# lane.net
KiCad netlist of a schematic drawn in Altium Designer
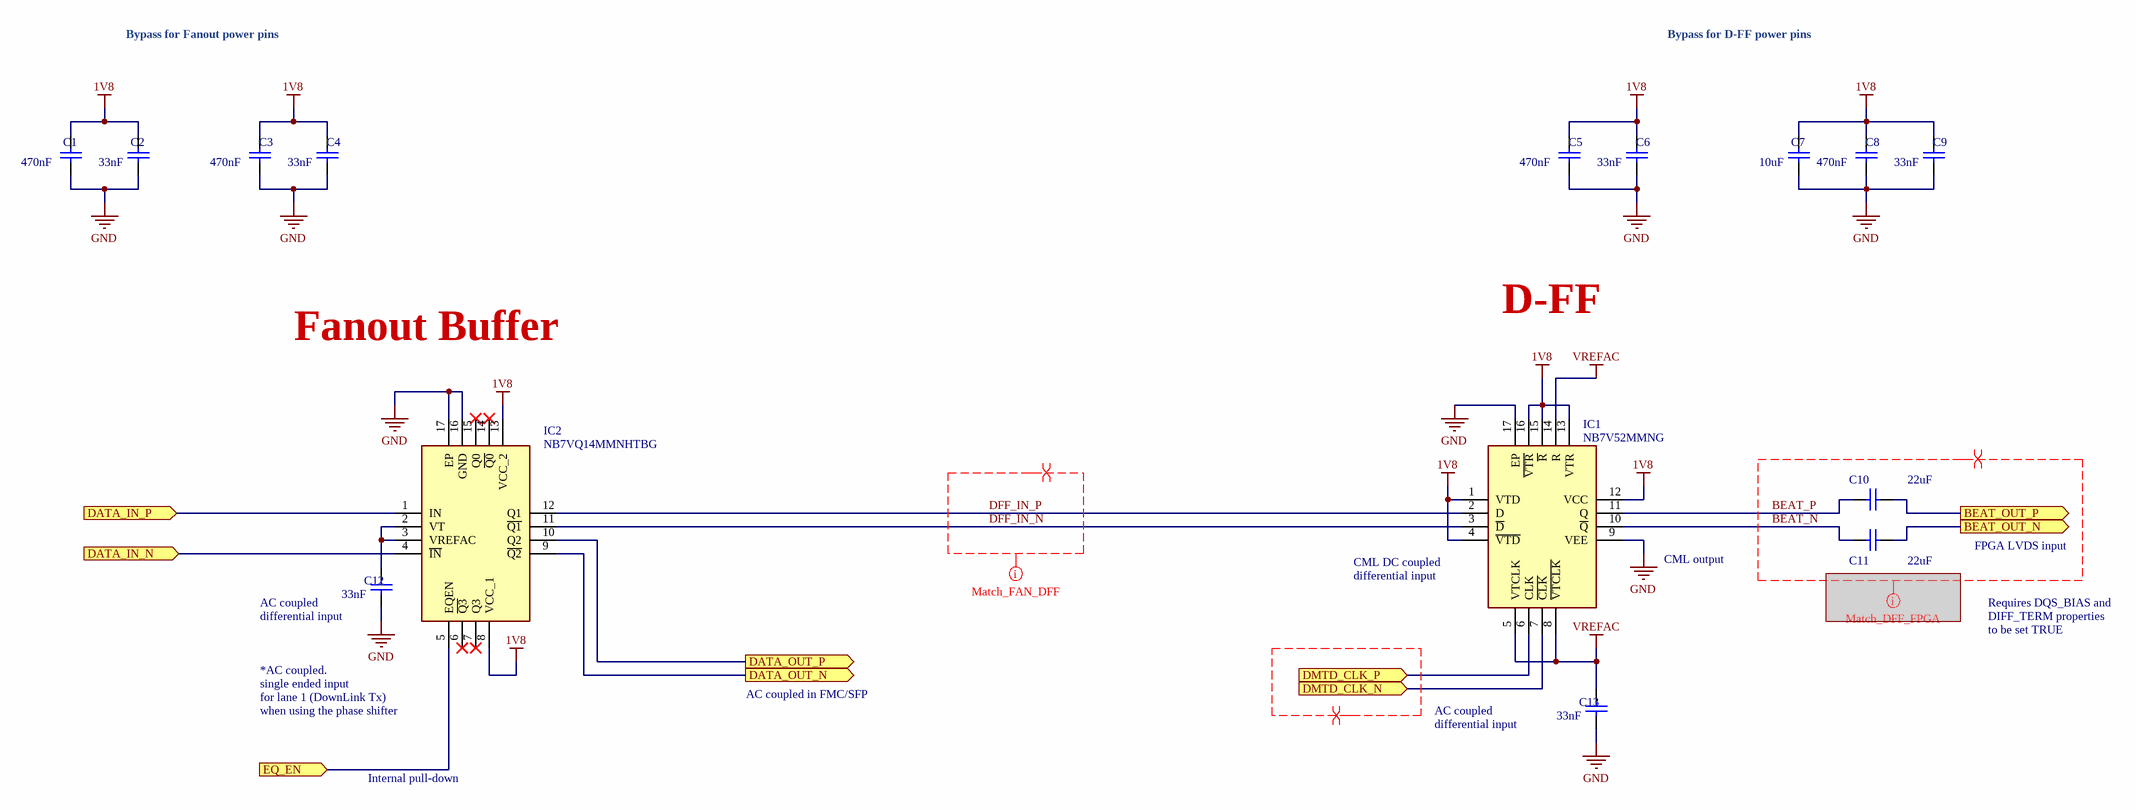
[diagram p0: lane.SchDoc]

(export (version "E")
  (design (tool "Eeschema 10.0.6"))
  (components
    (comp (ref "C1")
      (value "470nF")
      (footprint "CAPC0510X04N")
      (description "LLL153C70G474ME17")
      (libsource (lib "auxiliary_library") (part "Capacitor - non polarized"))
    )
    (comp (ref "C2")
      (value "33nF")
      (footprint "LLL03TR61E333KE01")
      (description "LLL03TR61E333KE01")
      (libsource (lib "auxiliary_library") (part "Capacitor - non polarized"))
    )
    (comp (ref "C3")
      (value "470nF")
      (footprint "CAPC0510X04N")
      (description "LLL153C70G474ME17")
      (libsource (lib "auxiliary_library") (part "Capacitor - non polarized"))
    )
    (comp (ref "C4")
      (value "33nF")
      (footprint "LLL03TR61E333KE01")
      (description "LLL03TR61E333KE01")
      (libsource (lib "auxiliary_library") (part "Capacitor - non polarized"))
    )
    (comp (ref "C5")
      (value "470nF")
      (footprint "CAPC0510X04N")
      (description "LLL153C70G474ME17")
      (libsource (lib "auxiliary_library") (part "Capacitor - non polarized"))
    )
    (comp (ref "C6")
      (value "33nF")
      (footprint "LLL03TR61E333KE01")
      (description "LLL03TR61E333KE01")
      (libsource (lib "auxiliary_library") (part "Capacitor - non polarized"))
    )
    (comp (ref "C7")
      (value "10uF")
      (footprint "CAPC1608X87N")
      (description "C1608X5R1E106M080AC")
      (fields
        (field (name "PART NUMBER") "CC0603_10UF_6.3V_20%_X5R")
        (field (name "VOLTAGE") "6.3V")
        (field (name "AUTHOR") "CERN DEM JLC")
      )
      (libsource (lib "Capacitors") (part "Capacitor - non polarized"))
    )
    (comp (ref "C8")
      (value "470nF")
      (footprint "CAPC0510X04N")
      (description "LLL153C70G474ME17")
      (libsource (lib "auxiliary_library") (part "Capacitor - non polarized"))
    )
    (comp (ref "C9")
      (value "33nF")
      (footprint "LLL03TR61E333KE01")
      (description "LLL03TR61E333KE01")
      (libsource (lib "auxiliary_library") (part "Capacitor - non polarized"))
    )
    (comp (ref "C10")
      (value "22uF")
      (footprint "MURATA_HI_DENSITY_0402_CAP")
      (description "GRM155R60J226ME11")
      (libsource (lib "schLib") (part "C0402-22uF-high-density"))
    )
    (comp (ref "C11")
      (value "22uF")
      (footprint "MURATA_HI_DENSITY_0402_CAP")
      (description "GRM155R60J226ME11")
      (libsource (lib "schLib") (part "C0402-22uF-high-density"))
    )
    (comp (ref "C12")
      (value "33nF")
      (footprint "LLL03TR61E333KE01")
      (description "LLL03TR61E333KE01")
      (libsource (lib "auxiliary_library") (part "Capacitor - non polarized"))
    )
    (comp (ref "C13")
      (value "33nF")
      (footprint "LLL03TR61E333KE01")
      (description "LLL03TR61E333KE01")
      (libsource (lib "auxiliary_library") (part "Capacitor - non polarized"))
    )
    (comp (ref "IC1")
      (value "NB7V52MMNG")
      (footprint "SamacSys:QFN50P300X300X100-17N")
      (description "Integrated Circuit")
      (fields (field (name "MOUSER PART NUMBER") "863-NB7V52MMNG"))
      (libsource (lib "SamacSys") (part "NB7V52MMNG"))
    )
    (comp (ref "IC2")
      (value "NB7VQ14MMNHTBG")
      (footprint "SamacSys:QFN50P300X300X100-17N")
      (description "Integrated Circuit")
      (fields (field (name "MOUSER PART NUMBER") "863-NB7VQ14MMNHTBG"))
      (libsource (lib "*") (part "NB7VQ14MMNHTBG"))
    )
  )
  (nets
    (net (code "1") (name "/BEAT_N") (class "Default")
      (node (ref "C11") (pin "2") (pinfunction "2_2") (pintype "passive"))
      (node (ref "IC1") (pin "10") (pinfunction "~{Q}_10") (pintype "passive"))
    )
    (net (code "2") (name "/BEAT_OUT_N") (class "Default")
      (node (ref "C11") (pin "1") (pinfunction "1_1") (pintype "passive"))
    )
    (net (code "3") (name "/BEAT_OUT_P") (class "Default")
      (node (ref "C10") (pin "1") (pinfunction "1_1") (pintype "passive"))
    )
    (net (code "4") (name "/BEAT_P") (class "Default")
      (node (ref "C10") (pin "2") (pinfunction "2_2") (pintype "passive"))
      (node (ref "IC1") (pin "11") (pinfunction "Q_11") (pintype "passive"))
    )
    (net (code "5") (name "/DATA_IN_N") (class "Default")
      (node (ref "IC2") (pin "4") (pinfunction "~{IN}_4") (pintype "passive"))
    )
    (net (code "6") (name "/DATA_IN_P") (class "Default")
      (node (ref "IC2") (pin "1") (pinfunction "IN_1") (pintype "passive"))
    )
    (net (code "7") (name "/DATA_OUT_N") (class "Default")
      (node (ref "IC2") (pin "9") (pinfunction "~{Q2}_9") (pintype "passive"))
    )
    (net (code "8") (name "/DATA_OUT_P") (class "Default")
      (node (ref "IC2") (pin "10") (pinfunction "Q2_10") (pintype "passive"))
    )
    (net (code "9") (name "/DFF_IN_N") (class "Default")
      (node (ref "IC1") (pin "3") (pinfunction "~{D}_3") (pintype "passive"))
      (node (ref "IC2") (pin "11") (pinfunction "~{Q1}_11") (pintype "passive"))
    )
    (net (code "10") (name "/DFF_IN_P") (class "Default")
      (node (ref "IC1") (pin "2") (pinfunction "D_2") (pintype "passive"))
      (node (ref "IC2") (pin "12") (pinfunction "Q1_12") (pintype "passive"))
    )
    (net (code "11") (name "/DMTD_CLK_N") (class "Default")
      (node (ref "IC1") (pin "7") (pinfunction "~{CLK}_7") (pintype "passive"))
    )
    (net (code "12") (name "/DMTD_CLK_P") (class "Default")
      (node (ref "IC1") (pin "6") (pinfunction "CLK_6") (pintype "passive"))
    )
    (net (code "13") (name "/EQ_EN") (class "Default")
      (node (ref "IC2") (pin "5") (pinfunction "EQEN_5") (pintype "passive"))
    )
    (net (code "14") (name "1V8") (class "Default")
      (node (ref "C1") (pin "2") (pinfunction "2_2") (pintype "passive"))
      (node (ref "C2") (pin "2") (pinfunction "2_2") (pintype "passive"))
      (node (ref "C3") (pin "2") (pinfunction "2_2") (pintype "passive"))
      (node (ref "C4") (pin "2") (pinfunction "2_2") (pintype "passive"))
      (node (ref "C5") (pin "2") (pinfunction "2_2") (pintype "passive"))
      (node (ref "C6") (pin "2") (pinfunction "2_2") (pintype "passive"))
      (node (ref "C7") (pin "2") (pinfunction "2_2") (pintype "passive"))
      (node (ref "C8") (pin "2") (pinfunction "2_2") (pintype "passive"))
      (node (ref "C9") (pin "2") (pinfunction "2_2") (pintype "passive"))
      (node (ref "IC1") (pin "1") (pinfunction "VTD_1") (pintype "passive"))
      (node (ref "IC1") (pin "12") (pinfunction "VCC_12") (pintype "passive"))
      (node (ref "IC1") (pin "13") (pinfunction "VTR_13") (pintype "passive"))
      (node (ref "IC1") (pin "15") (pinfunction "~{R}_15") (pintype "passive"))
      (node (ref "IC1") (pin "16") (pinfunction "~{VTR}_16") (pintype "passive"))
      (node (ref "IC1") (pin "4") (pinfunction "~{VTD}_4") (pintype "passive"))
      (node (ref "IC2") (pin "13") (pinfunction "VCC_2_13") (pintype "passive"))
      (node (ref "IC2") (pin "8") (pinfunction "VCC_1_8") (pintype "passive"))
    )
    (net (code "15") (name "GND") (class "Default")
      (node (ref "C1") (pin "1") (pinfunction "1_1") (pintype "passive"))
      (node (ref "C12") (pin "1") (pinfunction "1_1") (pintype "passive"))
      (node (ref "C13") (pin "1") (pinfunction "1_1") (pintype "passive"))
      (node (ref "C2") (pin "1") (pinfunction "1_1") (pintype "passive"))
      (node (ref "C3") (pin "1") (pinfunction "1_1") (pintype "passive"))
      (node (ref "C4") (pin "1") (pinfunction "1_1") (pintype "passive"))
      (node (ref "C5") (pin "1") (pinfunction "1_1") (pintype "passive"))
      (node (ref "C6") (pin "1") (pinfunction "1_1") (pintype "passive"))
      (node (ref "C7") (pin "1") (pinfunction "1_1") (pintype "passive"))
      (node (ref "C8") (pin "1") (pinfunction "1_1") (pintype "passive"))
      (node (ref "C9") (pin "1") (pinfunction "1_1") (pintype "passive"))
      (node (ref "IC1") (pin "17") (pinfunction "EP_17") (pintype "passive"))
      (node (ref "IC1") (pin "9") (pinfunction "VEE_9") (pintype "passive"))
      (node (ref "IC2") (pin "16") (pinfunction "GND_16") (pintype "passive"))
      (node (ref "IC2") (pin "17") (pinfunction "EP_17") (pintype "passive"))
    )
    (net (code "16") (name "Net-(IC2-VREFAC)") (class "Default")
      (node (ref "C12") (pin "2") (pinfunction "2_2") (pintype "passive"))
      (node (ref "IC2") (pin "2") (pinfunction "VT_2") (pintype "passive"))
      (node (ref "IC2") (pin "3") (pinfunction "VREFAC_3") (pintype "passive"))
    )
    (net (code "17") (name "VREFAC") (class "Default")
      (node (ref "C13") (pin "2") (pinfunction "2_2") (pintype "passive"))
      (node (ref "IC1") (pin "14") (pinfunction "R_14") (pintype "passive"))
      (node (ref "IC1") (pin "5") (pinfunction "VTCLK_5") (pintype "passive"))
      (node (ref "IC1") (pin "8") (pinfunction "~{VTCLK}_8") (pintype "passive"))
    )
    (net (code "18") (name "unconnected-(IC2-Q0-Pad15)") (class "Default")
      (node (ref "IC2") (pin "15") (pinfunction "Q0_15") (pintype "passive+no_connect"))
    )
    (net (code "19") (name "unconnected-(IC2-Q3-Pad7)") (class "Default")
      (node (ref "IC2") (pin "7") (pinfunction "Q3_7") (pintype "passive+no_connect"))
    )
    (net (code "20") (name "unconnected-(IC2-~{Q0}-Pad14)") (class "Default")
      (node (ref "IC2") (pin "14") (pinfunction "~{Q0}_14") (pintype "passive+no_connect"))
    )
    (net (code "21") (name "unconnected-(IC2-~{Q3}-Pad6)") (class "Default")
      (node (ref "IC2") (pin "6") (pinfunction "~{Q3}_6") (pintype "passive+no_connect"))
    )
  )
)
